# edge_dff_clk_low.net
KiCad netlist of a schematic drawn in Altium Designer
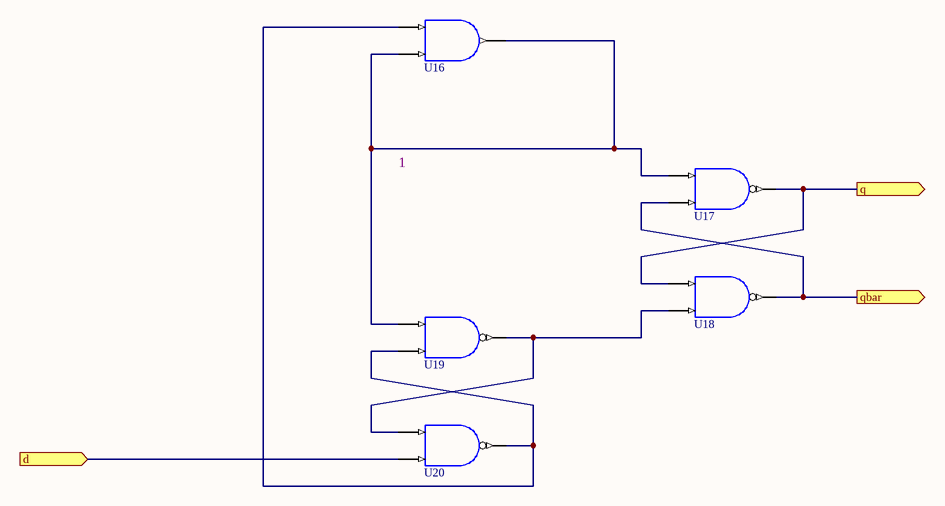
[diagram p0: edge_dff_clk_low.SchDoc]

(export (version "E")
  (design (tool "Eeschema 10.0.6"))
  (components
    (comp (ref "U16")
      (value "AND 2")
      (description "2 Input AND")
      (libsource (lib "BlockSchematics") (part "AND_2"))
    )
    (comp (ref "U17")
      (value "AND 2")
      (description "2 Input AND")
      (libsource (lib "BlockSchematics") (part "AND_2"))
    )
    (comp (ref "U18")
      (value "AND 2")
      (description "2 Input AND")
      (libsource (lib "BlockSchematics") (part "AND_2"))
    )
    (comp (ref "U19")
      (value "AND 2")
      (description "2 Input AND")
      (libsource (lib "BlockSchematics") (part "AND_2"))
    )
    (comp (ref "U20")
      (value "AND 2")
      (description "2 Input AND")
      (libsource (lib "BlockSchematics") (part "AND_2"))
    )
  )
  (nets
    (net (code "1") (name "/d") (class "Default")
      (node (ref "U20") (pin "B") (pinfunction "B_B") (pintype "input"))
    )
    (net (code "2") (name "/q") (class "Default")
      (node (ref "U17") (pin "Y") (pinfunction "Y_Y") (pintype "output"))
      (node (ref "U18") (pin "A") (pinfunction "A_A") (pintype "input"))
    )
    (net (code "3") (name "/qbar") (class "Default")
      (node (ref "U17") (pin "B") (pinfunction "B_B") (pintype "input"))
      (node (ref "U18") (pin "Y") (pinfunction "Y_Y") (pintype "output"))
    )
    (net (code "4") (name "Net-(U16-PadA)") (class "Default")
      (node (ref "U16") (pin "A") (pinfunction "A_A") (pintype "input"))
      (node (ref "U19") (pin "B") (pinfunction "B_B") (pintype "input"))
      (node (ref "U20") (pin "Y") (pinfunction "Y_Y") (pintype "output"))
    )
    (net (code "5") (name "Net-(U16-PadB)") (class "Default")
      (node (ref "U16") (pin "B") (pinfunction "B_B") (pintype "input"))
      (node (ref "U16") (pin "Y") (pinfunction "Y_Y") (pintype "output"))
      (node (ref "U17") (pin "A") (pinfunction "A_A") (pintype "input"))
      (node (ref "U19") (pin "A") (pinfunction "A_A") (pintype "input"))
    )
    (net (code "6") (name "Net-(U18-PadB)") (class "Default")
      (node (ref "U18") (pin "B") (pinfunction "B_B") (pintype "input"))
      (node (ref "U19") (pin "Y") (pinfunction "Y_Y") (pintype "output"))
      (node (ref "U20") (pin "A") (pinfunction "A_A") (pintype "input"))
    )
  )
)
